# LED_Panel.net
KiCad netlist of a schematic drawn in Altium Designer
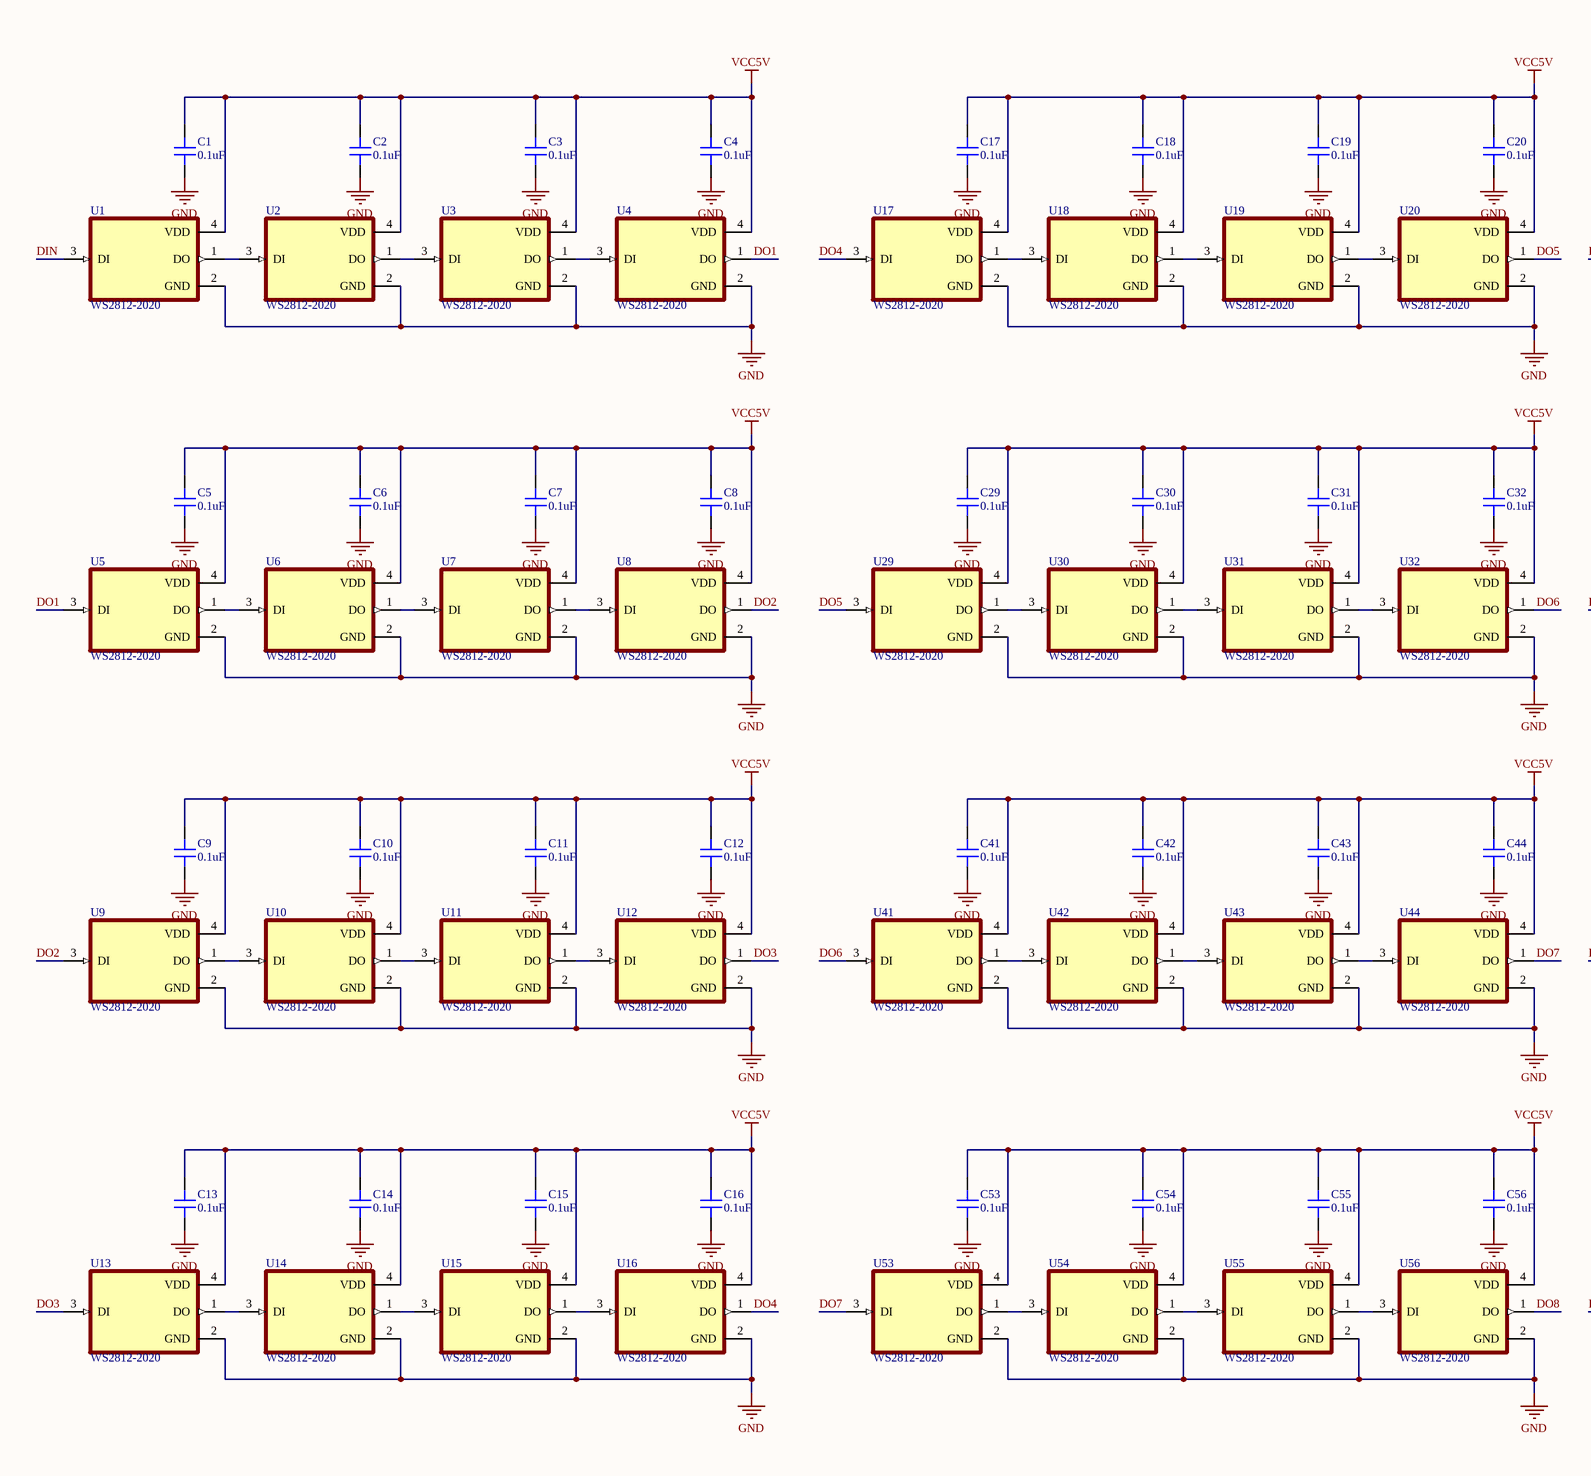
[diagram p0: LED_Panel.SchDoc, left]
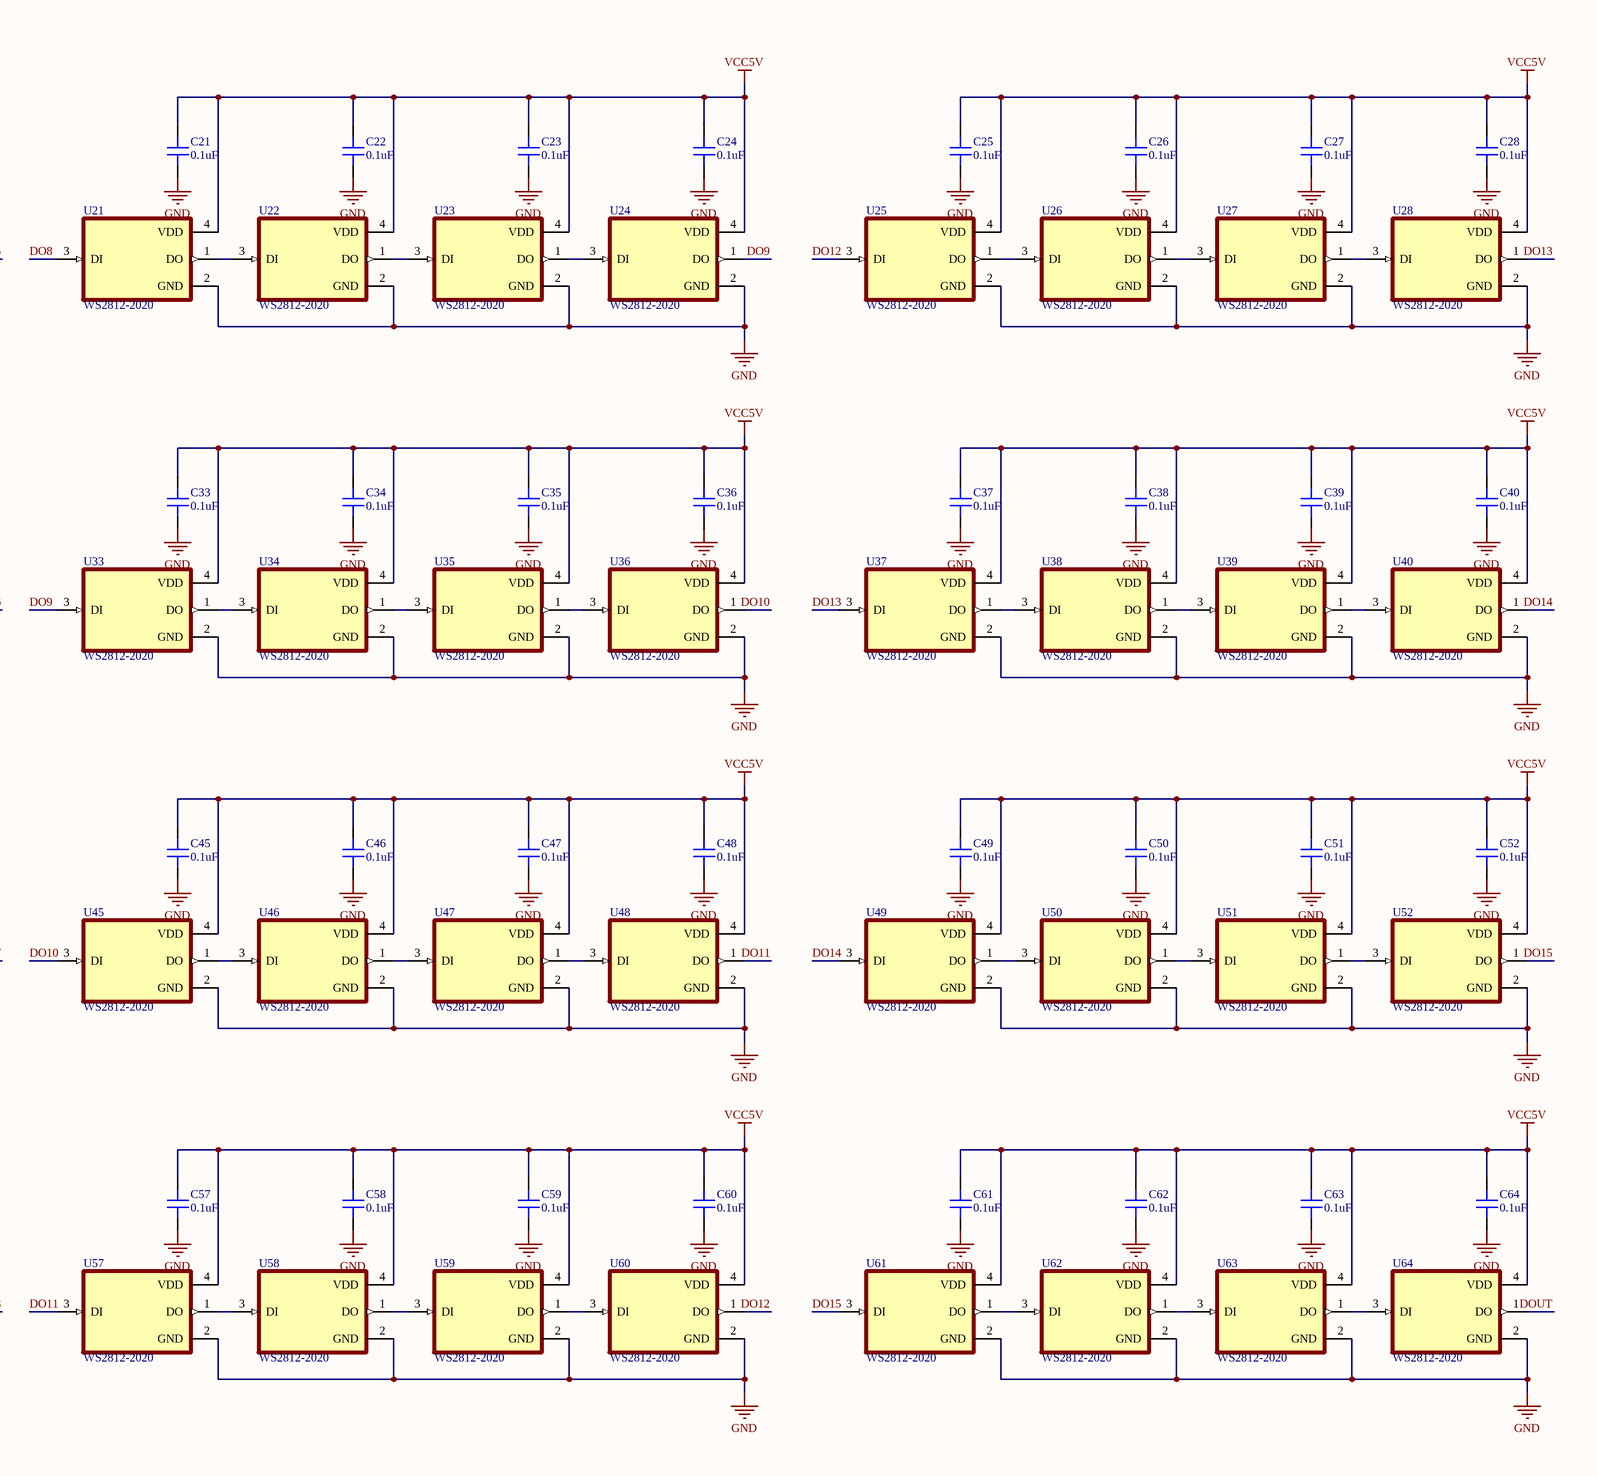
[diagram p1: LED_Panel.SchDoc, right]

(export (version "E")
  (design (tool "Eeschema 10.0.6"))
  (components
    (comp (ref "C1")
      (value "0.1uF")
      (footprint "CAP 0603_1608")
      (description "CAP CER 2700PF 25V NP0 0603")
      (fields
        (field (name "PART NUMBER") "C0603C272F3GAC7867")
        (field (name "MANUFACTURER") "KEMET")
        (field (name "LASTUPDATED") "2022/5/23 下午 12:55:07")
      )
      (libsource (lib "Celestial Altium Library - altium_library") (part "Capacitor"))
    )
    (comp (ref "C2")
      (value "0.1uF")
      (footprint "CAP 0603_1608")
      (description "CAP CER 2700PF 25V NP0 0603")
      (fields
        (field (name "PART NUMBER") "C0603C272F3GAC7867")
        (field (name "MANUFACTURER") "KEMET")
        (field (name "LASTUPDATED") "2022/5/23 下午 12:55:07")
      )
      (libsource (lib "Celestial Altium Library - altium_library") (part "Capacitor"))
    )
    (comp (ref "C3")
      (value "0.1uF")
      (footprint "CAP 0603_1608")
      (description "CAP CER 2700PF 25V NP0 0603")
      (fields
        (field (name "PART NUMBER") "C0603C272F3GAC7867")
        (field (name "MANUFACTURER") "KEMET")
        (field (name "LASTUPDATED") "2022/5/23 下午 12:55:07")
      )
      (libsource (lib "Celestial Altium Library - altium_library") (part "Capacitor"))
    )
    (comp (ref "C4")
      (value "0.1uF")
      (footprint "CAP 0603_1608")
      (description "CAP CER 2700PF 25V NP0 0603")
      (fields
        (field (name "PART NUMBER") "C0603C272F3GAC7867")
        (field (name "MANUFACTURER") "KEMET")
        (field (name "LASTUPDATED") "2022/5/23 下午 12:55:07")
      )
      (libsource (lib "Celestial Altium Library - altium_library") (part "Capacitor"))
    )
    (comp (ref "C5")
      (value "0.1uF")
      (footprint "CAP 0603_1608")
      (description "CAP CER 2700PF 25V NP0 0603")
      (fields
        (field (name "PART NUMBER") "C0603C272F3GAC7867")
        (field (name "MANUFACTURER") "KEMET")
        (field (name "LASTUPDATED") "2022/5/23 下午 12:55:07")
      )
      (libsource (lib "Celestial Altium Library - altium_library") (part "Capacitor"))
    )
    (comp (ref "C6")
      (value "0.1uF")
      (footprint "CAP 0603_1608")
      (description "CAP CER 2700PF 25V NP0 0603")
      (fields
        (field (name "PART NUMBER") "C0603C272F3GAC7867")
        (field (name "MANUFACTURER") "KEMET")
        (field (name "LASTUPDATED") "2022/5/23 下午 12:55:07")
      )
      (libsource (lib "Celestial Altium Library - altium_library") (part "Capacitor"))
    )
    (comp (ref "C7")
      (value "0.1uF")
      (footprint "CAP 0603_1608")
      (description "CAP CER 2700PF 25V NP0 0603")
      (fields
        (field (name "PART NUMBER") "C0603C272F3GAC7867")
        (field (name "MANUFACTURER") "KEMET")
        (field (name "LASTUPDATED") "2022/5/23 下午 12:55:07")
      )
      (libsource (lib "Celestial Altium Library - altium_library") (part "Capacitor"))
    )
    (comp (ref "C8")
      (value "0.1uF")
      (footprint "CAP 0603_1608")
      (description "CAP CER 2700PF 25V NP0 0603")
      (fields
        (field (name "PART NUMBER") "C0603C272F3GAC7867")
        (field (name "MANUFACTURER") "KEMET")
        (field (name "LASTUPDATED") "2022/5/23 下午 12:55:07")
      )
      (libsource (lib "Celestial Altium Library - altium_library") (part "Capacitor"))
    )
    (comp (ref "C9")
      (value "0.1uF")
      (footprint "CAP 0603_1608")
      (description "CAP CER 2700PF 25V NP0 0603")
      (fields
        (field (name "PART NUMBER") "C0603C272F3GAC7867")
        (field (name "MANUFACTURER") "KEMET")
        (field (name "LASTUPDATED") "2022/5/23 下午 12:55:07")
      )
      (libsource (lib "Celestial Altium Library - altium_library") (part "Capacitor"))
    )
    (comp (ref "C10")
      (value "0.1uF")
      (footprint "CAP 0603_1608")
      (description "CAP CER 2700PF 25V NP0 0603")
      (fields
        (field (name "PART NUMBER") "C0603C272F3GAC7867")
        (field (name "MANUFACTURER") "KEMET")
        (field (name "LASTUPDATED") "2022/5/23 下午 12:55:07")
      )
      (libsource (lib "Celestial Altium Library - altium_library") (part "Capacitor"))
    )
    (comp (ref "C11")
      (value "0.1uF")
      (footprint "CAP 0603_1608")
      (description "CAP CER 2700PF 25V NP0 0603")
      (fields
        (field (name "PART NUMBER") "C0603C272F3GAC7867")
        (field (name "MANUFACTURER") "KEMET")
        (field (name "LASTUPDATED") "2022/5/23 下午 12:55:07")
      )
      (libsource (lib "Celestial Altium Library - altium_library") (part "Capacitor"))
    )
    (comp (ref "C12")
      (value "0.1uF")
      (footprint "CAP 0603_1608")
      (description "CAP CER 2700PF 25V NP0 0603")
      (fields
        (field (name "PART NUMBER") "C0603C272F3GAC7867")
        (field (name "MANUFACTURER") "KEMET")
        (field (name "LASTUPDATED") "2022/5/23 下午 12:55:07")
      )
      (libsource (lib "Celestial Altium Library - altium_library") (part "Capacitor"))
    )
    (comp (ref "C13")
      (value "0.1uF")
      (footprint "CAP 0603_1608")
      (description "CAP CER 2700PF 25V NP0 0603")
      (fields
        (field (name "PART NUMBER") "C0603C272F3GAC7867")
        (field (name "MANUFACTURER") "KEMET")
        (field (name "LASTUPDATED") "2022/5/23 下午 12:55:07")
      )
      (libsource (lib "Celestial Altium Library - altium_library") (part "Capacitor"))
    )
    (comp (ref "C14")
      (value "0.1uF")
      (footprint "CAP 0603_1608")
      (description "CAP CER 2700PF 25V NP0 0603")
      (fields
        (field (name "PART NUMBER") "C0603C272F3GAC7867")
        (field (name "MANUFACTURER") "KEMET")
        (field (name "LASTUPDATED") "2022/5/23 下午 12:55:07")
      )
      (libsource (lib "Celestial Altium Library - altium_library") (part "Capacitor"))
    )
    (comp (ref "C15")
      (value "0.1uF")
      (footprint "CAP 0603_1608")
      (description "CAP CER 2700PF 25V NP0 0603")
      (fields
        (field (name "PART NUMBER") "C0603C272F3GAC7867")
        (field (name "MANUFACTURER") "KEMET")
        (field (name "LASTUPDATED") "2022/5/23 下午 12:55:07")
      )
      (libsource (lib "Celestial Altium Library - altium_library") (part "Capacitor"))
    )
    (comp (ref "C16")
      (value "0.1uF")
      (footprint "CAP 0603_1608")
      (description "CAP CER 2700PF 25V NP0 0603")
      (fields
        (field (name "PART NUMBER") "C0603C272F3GAC7867")
        (field (name "MANUFACTURER") "KEMET")
        (field (name "LASTUPDATED") "2022/5/23 下午 12:55:07")
      )
      (libsource (lib "Celestial Altium Library - altium_library") (part "Capacitor"))
    )
    (comp (ref "C17")
      (value "0.1uF")
      (footprint "CAP 0603_1608")
      (description "CAP CER 2700PF 25V NP0 0603")
      (fields
        (field (name "PART NUMBER") "C0603C272F3GAC7867")
        (field (name "MANUFACTURER") "KEMET")
        (field (name "LASTUPDATED") "2022/5/23 下午 12:55:07")
      )
      (libsource (lib "Celestial Altium Library - altium_library") (part "Capacitor"))
    )
    (comp (ref "C18")
      (value "0.1uF")
      (footprint "CAP 0603_1608")
      (description "CAP CER 2700PF 25V NP0 0603")
      (fields
        (field (name "PART NUMBER") "C0603C272F3GAC7867")
        (field (name "MANUFACTURER") "KEMET")
        (field (name "LASTUPDATED") "2022/5/23 下午 12:55:07")
      )
      (libsource (lib "Celestial Altium Library - altium_library") (part "Capacitor"))
    )
    (comp (ref "C19")
      (value "0.1uF")
      (footprint "CAP 0603_1608")
      (description "CAP CER 2700PF 25V NP0 0603")
      (fields
        (field (name "PART NUMBER") "C0603C272F3GAC7867")
        (field (name "MANUFACTURER") "KEMET")
        (field (name "LASTUPDATED") "2022/5/23 下午 12:55:07")
      )
      (libsource (lib "Celestial Altium Library - altium_library") (part "Capacitor"))
    )
    (comp (ref "C20")
      (value "0.1uF")
      (footprint "CAP 0603_1608")
      (description "CAP CER 2700PF 25V NP0 0603")
      (fields
        (field (name "PART NUMBER") "C0603C272F3GAC7867")
        (field (name "MANUFACTURER") "KEMET")
        (field (name "LASTUPDATED") "2022/5/23 下午 12:55:07")
      )
      (libsource (lib "Celestial Altium Library - altium_library") (part "Capacitor"))
    )
    (comp (ref "C21")
      (value "0.1uF")
      (footprint "CAP 0603_1608")
      (description "CAP CER 2700PF 25V NP0 0603")
      (fields
        (field (name "PART NUMBER") "C0603C272F3GAC7867")
        (field (name "MANUFACTURER") "KEMET")
        (field (name "LASTUPDATED") "2022/5/23 下午 12:55:07")
      )
      (libsource (lib "Celestial Altium Library - altium_library") (part "Capacitor"))
    )
    (comp (ref "C22")
      (value "0.1uF")
      (footprint "CAP 0603_1608")
      (description "CAP CER 2700PF 25V NP0 0603")
      (fields
        (field (name "PART NUMBER") "C0603C272F3GAC7867")
        (field (name "MANUFACTURER") "KEMET")
        (field (name "LASTUPDATED") "2022/5/23 下午 12:55:07")
      )
      (libsource (lib "Celestial Altium Library - altium_library") (part "Capacitor"))
    )
    (comp (ref "C23")
      (value "0.1uF")
      (footprint "CAP 0603_1608")
      (description "CAP CER 2700PF 25V NP0 0603")
      (fields
        (field (name "PART NUMBER") "C0603C272F3GAC7867")
        (field (name "MANUFACTURER") "KEMET")
        (field (name "LASTUPDATED") "2022/5/23 下午 12:55:07")
      )
      (libsource (lib "Celestial Altium Library - altium_library") (part "Capacitor"))
    )
    (comp (ref "C24")
      (value "0.1uF")
      (footprint "CAP 0603_1608")
      (description "CAP CER 2700PF 25V NP0 0603")
      (fields
        (field (name "PART NUMBER") "C0603C272F3GAC7867")
        (field (name "MANUFACTURER") "KEMET")
        (field (name "LASTUPDATED") "2022/5/23 下午 12:55:07")
      )
      (libsource (lib "Celestial Altium Library - altium_library") (part "Capacitor"))
    )
    (comp (ref "C25")
      (value "0.1uF")
      (footprint "CAP 0603_1608")
      (description "CAP CER 2700PF 25V NP0 0603")
      (fields
        (field (name "PART NUMBER") "C0603C272F3GAC7867")
        (field (name "MANUFACTURER") "KEMET")
        (field (name "LASTUPDATED") "2022/5/23 下午 12:55:07")
      )
      (libsource (lib "Celestial Altium Library - altium_library") (part "Capacitor"))
    )
    (comp (ref "C26")
      (value "0.1uF")
      (footprint "CAP 0603_1608")
      (description "CAP CER 2700PF 25V NP0 0603")
      (fields
        (field (name "PART NUMBER") "C0603C272F3GAC7867")
        (field (name "MANUFACTURER") "KEMET")
        (field (name "LASTUPDATED") "2022/5/23 下午 12:55:07")
      )
      (libsource (lib "Celestial Altium Library - altium_library") (part "Capacitor"))
    )
    (comp (ref "C27")
      (value "0.1uF")
      (footprint "CAP 0603_1608")
      (description "CAP CER 2700PF 25V NP0 0603")
      (fields
        (field (name "PART NUMBER") "C0603C272F3GAC7867")
        (field (name "MANUFACTURER") "KEMET")
        (field (name "LASTUPDATED") "2022/5/23 下午 12:55:07")
      )
      (libsource (lib "Celestial Altium Library - altium_library") (part "Capacitor"))
    )
    (comp (ref "C28")
      (value "0.1uF")
      (footprint "CAP 0603_1608")
      (description "CAP CER 2700PF 25V NP0 0603")
      (fields
        (field (name "PART NUMBER") "C0603C272F3GAC7867")
        (field (name "MANUFACTURER") "KEMET")
        (field (name "LASTUPDATED") "2022/5/23 下午 12:55:07")
      )
      (libsource (lib "Celestial Altium Library - altium_library") (part "Capacitor"))
    )
    (comp (ref "C29")
      (value "0.1uF")
      (footprint "CAP 0603_1608")
      (description "CAP CER 2700PF 25V NP0 0603")
      (fields
        (field (name "PART NUMBER") "C0603C272F3GAC7867")
        (field (name "MANUFACTURER") "KEMET")
        (field (name "LASTUPDATED") "2022/5/23 下午 12:55:07")
      )
      (libsource (lib "Celestial Altium Library - altium_library") (part "Capacitor"))
    )
    (comp (ref "C30")
      (value "0.1uF")
      (footprint "CAP 0603_1608")
      (description "CAP CER 2700PF 25V NP0 0603")
      (fields
        (field (name "PART NUMBER") "C0603C272F3GAC7867")
        (field (name "MANUFACTURER") "KEMET")
        (field (name "LASTUPDATED") "2022/5/23 下午 12:55:07")
      )
      (libsource (lib "Celestial Altium Library - altium_library") (part "Capacitor"))
    )
    (comp (ref "C31")
      (value "0.1uF")
      (footprint "CAP 0603_1608")
      (description "CAP CER 2700PF 25V NP0 0603")
      (fields
        (field (name "PART NUMBER") "C0603C272F3GAC7867")
        (field (name "MANUFACTURER") "KEMET")
        (field (name "LASTUPDATED") "2022/5/23 下午 12:55:07")
      )
      (libsource (lib "Celestial Altium Library - altium_library") (part "Capacitor"))
    )
    (comp (ref "C32")
      (value "0.1uF")
      (footprint "CAP 0603_1608")
      (description "CAP CER 2700PF 25V NP0 0603")
      (fields
        (field (name "PART NUMBER") "C0603C272F3GAC7867")
        (field (name "MANUFACTURER") "KEMET")
        (field (name "LASTUPDATED") "2022/5/23 下午 12:55:07")
      )
      (libsource (lib "Celestial Altium Library - altium_library") (part "Capacitor"))
    )
    (comp (ref "C33")
      (value "0.1uF")
      (footprint "CAP 0603_1608")
      (description "CAP CER 2700PF 25V NP0 0603")
      (fields
        (field (name "PART NUMBER") "C0603C272F3GAC7867")
        (field (name "MANUFACTURER") "KEMET")
        (field (name "LASTUPDATED") "2022/5/23 下午 12:55:07")
      )
      (libsource (lib "Celestial Altium Library - altium_library") (part "Capacitor"))
    )
    (comp (ref "C34")
      (value "0.1uF")
      (footprint "CAP 0603_1608")
      (description "CAP CER 2700PF 25V NP0 0603")
      (fields
        (field (name "PART NUMBER") "C0603C272F3GAC7867")
        (field (name "MANUFACTURER") "KEMET")
        (field (name "LASTUPDATED") "2022/5/23 下午 12:55:07")
      )
      (libsource (lib "Celestial Altium Library - altium_library") (part "Capacitor"))
    )
    (comp (ref "C35")
      (value "0.1uF")
      (footprint "CAP 0603_1608")
      (description "CAP CER 2700PF 25V NP0 0603")
      (fields
        (field (name "PART NUMBER") "C0603C272F3GAC7867")
        (field (name "MANUFACTURER") "KEMET")
        (field (name "LASTUPDATED") "2022/5/23 下午 12:55:07")
      )
      (libsource (lib "Celestial Altium Library - altium_library") (part "Capacitor"))
    )
    (comp (ref "C36")
      (value "0.1uF")
      (footprint "CAP 0603_1608")
      (description "CAP CER 2700PF 25V NP0 0603")
      (fields
        (field (name "PART NUMBER") "C0603C272F3GAC7867")
        (field (name "MANUFACTURER") "KEMET")
        (field (name "LASTUPDATED") "2022/5/23 下午 12:55:07")
      )
      (libsource (lib "Celestial Altium Library - altium_library") (part "Capacitor"))
    )
    (comp (ref "C37")
      (value "0.1uF")
      (footprint "CAP 0603_1608")
      (description "CAP CER 2700PF 25V NP0 0603")
      (fields
        (field (name "PART NUMBER") "C0603C272F3GAC7867")
        (field (name "MANUFACTURER") "KEMET")
        (field (name "LASTUPDATED") "2022/5/23 下午 12:55:07")
      )
      (libsource (lib "Celestial Altium Library - altium_library") (part "Capacitor"))
    )
    (comp (ref "C38")
      (value "0.1uF")
      (footprint "CAP 0603_1608")
      (description "CAP CER 2700PF 25V NP0 0603")
      (fields
        (field (name "PART NUMBER") "C0603C272F3GAC7867")
        (field (name "MANUFACTURER") "KEMET")
        (field (name "LASTUPDATED") "2022/5/23 下午 12:55:07")
      )
      (libsource (lib "Celestial Altium Library - altium_library") (part "Capacitor"))
    )
    (comp (ref "C39")
      (value "0.1uF")
      (footprint "CAP 0603_1608")
      (description "CAP CER 2700PF 25V NP0 0603")
      (fields
        (field (name "PART NUMBER") "C0603C272F3GAC7867")
        (field (name "MANUFACTURER") "KEMET")
        (field (name "LASTUPDATED") "2022/5/23 下午 12:55:07")
      )
      (libsource (lib "Celestial Altium Library - altium_library") (part "Capacitor"))
    )
    (comp (ref "C40")
      (value "0.1uF")
      (footprint "CAP 0603_1608")
      (description "CAP CER 2700PF 25V NP0 0603")
      (fields
        (field (name "PART NUMBER") "C0603C272F3GAC7867")
        (field (name "MANUFACTURER") "KEMET")
        (field (name "LASTUPDATED") "2022/5/23 下午 12:55:07")
      )
      (libsource (lib "Celestial Altium Library - altium_library") (part "Capacitor"))
    )
    (comp (ref "C41")
      (value "0.1uF")
      (footprint "CAP 0603_1608")
      (description "CAP CER 2700PF 25V NP0 0603")
      (fields
        (field (name "PART NUMBER") "C0603C272F3GAC7867")
        (field (name "MANUFACTURER") "KEMET")
        (field (name "LASTUPDATED") "2022/5/23 下午 12:55:07")
      )
      (libsource (lib "Celestial Altium Library - altium_library") (part "Capacitor"))
    )
    (comp (ref "C42")
      (value "0.1uF")
      (footprint "CAP 0603_1608")
      (description "CAP CER 2700PF 25V NP0 0603")
      (fields
        (field (name "PART NUMBER") "C0603C272F3GAC7867")
        (field (name "MANUFACTURER") "KEMET")
        (field (name "LASTUPDATED") "2022/5/23 下午 12:55:07")
      )
      (libsource (lib "Celestial Altium Library - altium_library") (part "Capacitor"))
    )
    (comp (ref "C43")
      (value "0.1uF")
      (footprint "CAP 0603_1608")
      (description "CAP CER 2700PF 25V NP0 0603")
      (fields
        (field (name "PART NUMBER") "C0603C272F3GAC7867")
        (field (name "MANUFACTURER") "KEMET")
        (field (name "LASTUPDATED") "2022/5/23 下午 12:55:07")
      )
      (libsource (lib "Celestial Altium Library - altium_library") (part "Capacitor"))
    )
    (comp (ref "C44")
      (value "0.1uF")
      (footprint "CAP 0603_1608")
      (description "CAP CER 2700PF 25V NP0 0603")
      (fields
        (field (name "PART NUMBER") "C0603C272F3GAC7867")
        (field (name "MANUFACTURER") "KEMET")
        (field (name "LASTUPDATED") "2022/5/23 下午 12:55:07")
      )
      (libsource (lib "Celestial Altium Library - altium_library") (part "Capacitor"))
    )
    (comp (ref "C45")
      (value "0.1uF")
      (footprint "CAP 0603_1608")
      (description "CAP CER 2700PF 25V NP0 0603")
      (fields
        (field (name "PART NUMBER") "C0603C272F3GAC7867")
        (field (name "MANUFACTURER") "KEMET")
        (field (name "LASTUPDATED") "2022/5/23 下午 12:55:07")
      )
      (libsource (lib "Celestial Altium Library - altium_library") (part "Capacitor"))
    )
    (comp (ref "C46")
      (value "0.1uF")
      (footprint "CAP 0603_1608")
      (description "CAP CER 2700PF 25V NP0 0603")
      (fields
        (field (name "PART NUMBER") "C0603C272F3GAC7867")
        (field (name "MANUFACTURER") "KEMET")
        (field (name "LASTUPDATED") "2022/5/23 下午 12:55:07")
      )
      (libsource (lib "Celestial Altium Library - altium_library") (part "Capacitor"))
    )
    (comp (ref "C47")
      (value "0.1uF")
      (footprint "CAP 0603_1608")
      (description "CAP CER 2700PF 25V NP0 0603")
      (fields
        (field (name "PART NUMBER") "C0603C272F3GAC7867")
        (field (name "MANUFACTURER") "KEMET")
        (field (name "LASTUPDATED") "2022/5/23 下午 12:55:07")
      )
      (libsource (lib "Celestial Altium Library - altium_library") (part "Capacitor"))
    )
    (comp (ref "C48")
      (value "0.1uF")
      (footprint "CAP 0603_1608")
      (description "CAP CER 2700PF 25V NP0 0603")
      (fields
        (field (name "PART NUMBER") "C0603C272F3GAC7867")
        (field (name "MANUFACTURER") "KEMET")
        (field (name "LASTUPDATED") "2022/5/23 下午 12:55:07")
      )
      (libsource (lib "Celestial Altium Library - altium_library") (part "Capacitor"))
    )
    (comp (ref "C49")
      (value "0.1uF")
      (footprint "CAP 0603_1608")
      (description "CAP CER 2700PF 25V NP0 0603")
      (fields
        (field (name "PART NUMBER") "C0603C272F3GAC7867")
        (field (name "MANUFACTURER") "KEMET")
        (field (name "LASTUPDATED") "2022/5/23 下午 12:55:07")
      )
      (libsource (lib "Celestial Altium Library - altium_library") (part "Capacitor"))
    )
    (comp (ref "C50")
      (value "0.1uF")
      (footprint "CAP 0603_1608")
      (description "CAP CER 2700PF 25V NP0 0603")
      (fields
        (field (name "PART NUMBER") "C0603C272F3GAC7867")
        (field (name "MANUFACTURER") "KEMET")
        (field (name "LASTUPDATED") "2022/5/23 下午 12:55:07")
      )
      (libsource (lib "Celestial Altium Library - altium_library") (part "Capacitor"))
    )
    (comp (ref "C51")
      (value "0.1uF")
      (footprint "CAP 0603_1608")
      (description "CAP CER 2700PF 25V NP0 0603")
      (fields
        (field (name "PART NUMBER") "C0603C272F3GAC7867")
        (field (name "MANUFACTURER") "KEMET")
        (field (name "LASTUPDATED") "2022/5/23 下午 12:55:07")
      )
      (libsource (lib "Celestial Altium Library - altium_library") (part "Capacitor"))
    )
    (comp (ref "C52")
      (value "0.1uF")
      (footprint "CAP 0603_1608")
      (description "CAP CER 2700PF 25V NP0 0603")
      (fields
        (field (name "PART NUMBER") "C0603C272F3GAC7867")
        (field (name "MANUFACTURER") "KEMET")
        (field (name "LASTUPDATED") "2022/5/23 下午 12:55:07")
      )
      (libsource (lib "Celestial Altium Library - altium_library") (part "Capacitor"))
    )
    (comp (ref "C53")
      (value "0.1uF")
      (footprint "CAP 0603_1608")
      (description "CAP CER 2700PF 25V NP0 0603")
      (fields
        (field (name "PART NUMBER") "C0603C272F3GAC7867")
        (field (name "MANUFACTURER") "KEMET")
        (field (name "LASTUPDATED") "2022/5/23 下午 12:55:07")
      )
      (libsource (lib "Celestial Altium Library - altium_library") (part "Capacitor"))
    )
    (comp (ref "C54")
      (value "0.1uF")
      (footprint "CAP 0603_1608")
      (description "CAP CER 2700PF 25V NP0 0603")
      (fields
        (field (name "PART NUMBER") "C0603C272F3GAC7867")
        (field (name "MANUFACTURER") "KEMET")
        (field (name "LASTUPDATED") "2022/5/23 下午 12:55:07")
      )
      (libsource (lib "Celestial Altium Library - altium_library") (part "Capacitor"))
    )
    (comp (ref "C55")
      (value "0.1uF")
      (footprint "CAP 0603_1608")
      (description "CAP CER 2700PF 25V NP0 0603")
      (fields
        (field (name "PART NUMBER") "C0603C272F3GAC7867")
        (field (name "MANUFACTURER") "KEMET")
        (field (name "LASTUPDATED") "2022/5/23 下午 12:55:07")
      )
      (libsource (lib "Celestial Altium Library - altium_library") (part "Capacitor"))
    )
    (comp (ref "C56")
      (value "0.1uF")
      (footprint "CAP 0603_1608")
      (description "CAP CER 2700PF 25V NP0 0603")
      (fields
        (field (name "PART NUMBER") "C0603C272F3GAC7867")
        (field (name "MANUFACTURER") "KEMET")
        (field (name "LASTUPDATED") "2022/5/23 下午 12:55:07")
      )
      (libsource (lib "Celestial Altium Library - altium_library") (part "Capacitor"))
    )
    (comp (ref "C57")
      (value "0.1uF")
      (footprint "CAP 0603_1608")
      (description "CAP CER 2700PF 25V NP0 0603")
      (fields
        (field (name "PART NUMBER") "C0603C272F3GAC7867")
        (field (name "MANUFACTURER") "KEMET")
        (field (name "LASTUPDATED") "2022/5/23 下午 12:55:07")
      )
      (libsource (lib "Celestial Altium Library - altium_library") (part "Capacitor"))
    )
    (comp (ref "C58")
      (value "0.1uF")
      (footprint "CAP 0603_1608")
      (description "CAP CER 2700PF 25V NP0 0603")
      (fields
        (field (name "PART NUMBER") "C0603C272F3GAC7867")
        (field (name "MANUFACTURER") "KEMET")
        (field (name "LASTUPDATED") "2022/5/23 下午 12:55:07")
      )
      (libsource (lib "Celestial Altium Library - altium_library") (part "Capacitor"))
    )
    (comp (ref "C59")
      (value "0.1uF")
      (footprint "CAP 0603_1608")
      (description "CAP CER 2700PF 25V NP0 0603")
      (fields
        (field (name "PART NUMBER") "C0603C272F3GAC7867")
        (field (name "MANUFACTURER") "KEMET")
        (field (name "LASTUPDATED") "2022/5/23 下午 12:55:07")
      )
      (libsource (lib "Celestial Altium Library - altium_library") (part "Capacitor"))
    )
    (comp (ref "C60")
      (value "0.1uF")
      (footprint "CAP 0603_1608")
      (description "CAP CER 2700PF 25V NP0 0603")
      (fields
        (field (name "PART NUMBER") "C0603C272F3GAC7867")
        (field (name "MANUFACTURER") "KEMET")
        (field (name "LASTUPDATED") "2022/5/23 下午 12:55:07")
      )
      (libsource (lib "Celestial Altium Library - altium_library") (part "Capacitor"))
    )
    (comp (ref "C61")
      (value "0.1uF")
      (footprint "CAP 0603_1608")
      (description "CAP CER 2700PF 25V NP0 0603")
      (fields
        (field (name "PART NUMBER") "C0603C272F3GAC7867")
        (field (name "MANUFACTURER") "KEMET")
        (field (name "LASTUPDATED") "2022/5/23 下午 12:55:07")
      )
      (libsource (lib "Celestial Altium Library - altium_library") (part "Capacitor"))
    )
    (comp (ref "C62")
      (value "0.1uF")
      (footprint "CAP 0603_1608")
      (description "CAP CER 2700PF 25V NP0 0603")
      (fields
        (field (name "PART NUMBER") "C0603C272F3GAC7867")
        (field (name "MANUFACTURER") "KEMET")
        (field (name "LASTUPDATED") "2022/5/23 下午 12:55:07")
      )
      (libsource (lib "Celestial Altium Library - altium_library") (part "Capacitor"))
    )
    (comp (ref "C63")
      (value "0.1uF")
      (footprint "CAP 0603_1608")
      (description "CAP CER 2700PF 25V NP0 0603")
      (fields
        (field (name "PART NUMBER") "C0603C272F3GAC7867")
        (field (name "MANUFACTURER") "KEMET")
        (field (name "LASTUPDATED") "2022/5/23 下午 12:55:07")
      )
      (libsource (lib "Celestial Altium Library - altium_library") (part "Capacitor"))
    )
    (comp (ref "C64")
      (value "0.1uF")
      (footprint "CAP 0603_1608")
      (description "CAP CER 2700PF 25V NP0 0603")
      (fields
        (field (name "PART NUMBER") "C0603C272F3GAC7867")
        (field (name "MANUFACTURER") "KEMET")
        (field (name "LASTUPDATED") "2022/5/23 下午 12:55:07")
      )
      (libsource (lib "Celestial Altium Library - altium_library") (part "Capacitor"))
    )
    (comp (ref "U1")
      (value "WS2812-2020")
      (footprint "LED_WS2812-2020")
      (fields (field (name "MF") "{'manufacturer': u'Worldsemi'}"))
      (libsource (lib "SnapEDA_Library") (part "WS2812-2020"))
    )
    (comp (ref "U2")
      (value "WS2812-2020")
      (footprint "LED_WS2812-2020")
      (fields (field (name "MF") "{'manufacturer': u'Worldsemi'}"))
      (libsource (lib "SnapEDA_Library") (part "WS2812-2020"))
    )
    (comp (ref "U3")
      (value "WS2812-2020")
      (footprint "LED_WS2812-2020")
      (fields (field (name "MF") "{'manufacturer': u'Worldsemi'}"))
      (libsource (lib "SnapEDA_Library") (part "WS2812-2020"))
    )
    (comp (ref "U4")
      (value "WS2812-2020")
      (footprint "LED_WS2812-2020")
      (fields (field (name "MF") "{'manufacturer': u'Worldsemi'}"))
      (libsource (lib "SnapEDA_Library") (part "WS2812-2020"))
    )
    (comp (ref "U5")
      (value "WS2812-2020")
      (footprint "LED_WS2812-2020")
      (fields (field (name "MF") "{'manufacturer': u'Worldsemi'}"))
      (libsource (lib "SnapEDA_Library") (part "WS2812-2020"))
    )
    (comp (ref "U6")
      (value "WS2812-2020")
      (footprint "LED_WS2812-2020")
      (fields (field (name "MF") "{'manufacturer': u'Worldsemi'}"))
      (libsource (lib "SnapEDA_Library") (part "WS2812-2020"))
    )
    (comp (ref "U7")
      (value "WS2812-2020")
      (footprint "LED_WS2812-2020")
      (fields (field (name "MF") "{'manufacturer': u'Worldsemi'}"))
      (libsource (lib "SnapEDA_Library") (part "WS2812-2020"))
    )
    (comp (ref "U8")
      (value "WS2812-2020")
      (footprint "LED_WS2812-2020")
      (fields (field (name "MF") "{'manufacturer': u'Worldsemi'}"))
      (libsource (lib "SnapEDA_Library") (part "WS2812-2020"))
    )
    (comp (ref "U9")
      (value "WS2812-2020")
      (footprint "LED_WS2812-2020")
      (fields (field (name "MF") "{'manufacturer': u'Worldsemi'}"))
      (libsource (lib "SnapEDA_Library") (part "WS2812-2020"))
    )
    (comp (ref "U10")
      (value "WS2812-2020")
      (footprint "LED_WS2812-2020")
      (fields (field (name "MF") "{'manufacturer': u'Worldsemi'}"))
      (libsource (lib "SnapEDA_Library") (part "WS2812-2020"))
    )
    (comp (ref "U11")
      (value "WS2812-2020")
      (footprint "LED_WS2812-2020")
      (fields (field (name "MF") "{'manufacturer': u'Worldsemi'}"))
      (libsource (lib "SnapEDA_Library") (part "WS2812-2020"))
    )
    (comp (ref "U12")
      (value "WS2812-2020")
      (footprint "LED_WS2812-2020")
      (fields (field (name "MF") "{'manufacturer': u'Worldsemi'}"))
      (libsource (lib "SnapEDA_Library") (part "WS2812-2020"))
    )
    (comp (ref "U13")
      (value "WS2812-2020")
      (footprint "LED_WS2812-2020")
      (fields (field (name "MF") "{'manufacturer': u'Worldsemi'}"))
      (libsource (lib "SnapEDA_Library") (part "WS2812-2020"))
    )
    (comp (ref "U14")
      (value "WS2812-2020")
      (footprint "LED_WS2812-2020")
      (fields (field (name "MF") "{'manufacturer': u'Worldsemi'}"))
      (libsource (lib "SnapEDA_Library") (part "WS2812-2020"))
    )
    (comp (ref "U15")
      (value "WS2812-2020")
      (footprint "LED_WS2812-2020")
      (fields (field (name "MF") "{'manufacturer': u'Worldsemi'}"))
      (libsource (lib "SnapEDA_Library") (part "WS2812-2020"))
    )
    (comp (ref "U16")
      (value "WS2812-2020")
      (footprint "LED_WS2812-2020")
      (fields (field (name "MF") "{'manufacturer': u'Worldsemi'}"))
      (libsource (lib "SnapEDA_Library") (part "WS2812-2020"))
    )
    (comp (ref "U17")
      (value "WS2812-2020")
      (footprint "LED_WS2812-2020")
      (fields (field (name "MF") "{'manufacturer': u'Worldsemi'}"))
      (libsource (lib "SnapEDA_Library") (part "WS2812-2020"))
    )
    (comp (ref "U18")
      (value "WS2812-2020")
      (footprint "LED_WS2812-2020")
      (fields (field (name "MF") "{'manufacturer': u'Worldsemi'}"))
      (libsource (lib "SnapEDA_Library") (part "WS2812-2020"))
    )
    (comp (ref "U19")
      (value "WS2812-2020")
      (footprint "LED_WS2812-2020")
      (fields (field (name "MF") "{'manufacturer': u'Worldsemi'}"))
      (libsource (lib "SnapEDA_Library") (part "WS2812-2020"))
    )
    (comp (ref "U20")
      (value "WS2812-2020")
      (footprint "LED_WS2812-2020")
      (fields (field (name "MF") "{'manufacturer': u'Worldsemi'}"))
      (libsource (lib "SnapEDA_Library") (part "WS2812-2020"))
    )
    (comp (ref "U21")
      (value "WS2812-2020")
      (footprint "LED_WS2812-2020")
      (fields (field (name "MF") "{'manufacturer': u'Worldsemi'}"))
      (libsource (lib "SnapEDA_Library") (part "WS2812-2020"))
    )
    (comp (ref "U22")
      (value "WS2812-2020")
      (footprint "LED_WS2812-2020")
      (fields (field (name "MF") "{'manufacturer': u'Worldsemi'}"))
      (libsource (lib "SnapEDA_Library") (part "WS2812-2020"))
    )
    (comp (ref "U23")
      (value "WS2812-2020")
      (footprint "LED_WS2812-2020")
      (fields (field (name "MF") "{'manufacturer': u'Worldsemi'}"))
      (libsource (lib "SnapEDA_Library") (part "WS2812-2020"))
    )
    (comp (ref "U24")
      (value "WS2812-2020")
      (footprint "LED_WS2812-2020")
      (fields (field (name "MF") "{'manufacturer': u'Worldsemi'}"))
      (libsource (lib "SnapEDA_Library") (part "WS2812-2020"))
    )
    (comp (ref "U25")
      (value "WS2812-2020")
      (footprint "LED_WS2812-2020")
      (fields (field (name "MF") "{'manufacturer': u'Worldsemi'}"))
      (libsource (lib "SnapEDA_Library") (part "WS2812-2020"))
    )
    (comp (ref "U26")
      (value "WS2812-2020")
      (footprint "LED_WS2812-2020")
      (fields (field (name "MF") "{'manufacturer': u'Worldsemi'}"))
      (libsource (lib "SnapEDA_Library") (part "WS2812-2020"))
    )
    (comp (ref "U27")
      (value "WS2812-2020")
      (footprint "LED_WS2812-2020")
      (fields (field (name "MF") "{'manufacturer': u'Worldsemi'}"))
      (libsource (lib "SnapEDA_Library") (part "WS2812-2020"))
    )
    (comp (ref "U28")
      (value "WS2812-2020")
      (footprint "LED_WS2812-2020")
      (fields (field (name "MF") "{'manufacturer': u'Worldsemi'}"))
      (libsource (lib "SnapEDA_Library") (part "WS2812-2020"))
    )
    (comp (ref "U29")
      (value "WS2812-2020")
      (footprint "LED_WS2812-2020")
      (fields (field (name "MF") "{'manufacturer': u'Worldsemi'}"))
      (libsource (lib "SnapEDA_Library") (part "WS2812-2020"))
    )
    (comp (ref "U30")
      (value "WS2812-2020")
      (footprint "LED_WS2812-2020")
      (fields (field (name "MF") "{'manufacturer': u'Worldsemi'}"))
      (libsource (lib "SnapEDA_Library") (part "WS2812-2020"))
    )
    (comp (ref "U31")
      (value "WS2812-2020")
      (footprint "LED_WS2812-2020")
      (fields (field (name "MF") "{'manufacturer': u'Worldsemi'}"))
      (libsource (lib "SnapEDA_Library") (part "WS2812-2020"))
    )
    (comp (ref "U32")
      (value "WS2812-2020")
      (footprint "LED_WS2812-2020")
      (fields (field (name "MF") "{'manufacturer': u'Worldsemi'}"))
      (libsource (lib "SnapEDA_Library") (part "WS2812-2020"))
    )
    (comp (ref "U33")
      (value "WS2812-2020")
      (footprint "LED_WS2812-2020")
      (fields (field (name "MF") "{'manufacturer': u'Worldsemi'}"))
      (libsource (lib "SnapEDA_Library") (part "WS2812-2020"))
    )
    (comp (ref "U34")
      (value "WS2812-2020")
      (footprint "LED_WS2812-2020")
      (fields (field (name "MF") "{'manufacturer': u'Worldsemi'}"))
      (libsource (lib "SnapEDA_Library") (part "WS2812-2020"))
    )
    (comp (ref "U35")
      (value "WS2812-2020")
      (footprint "LED_WS2812-2020")
      (fields (field (name "MF") "{'manufacturer': u'Worldsemi'}"))
      (libsource (lib "SnapEDA_Library") (part "WS2812-2020"))
    )
    (comp (ref "U36")
      (value "WS2812-2020")
      (footprint "LED_WS2812-2020")
      (fields (field (name "MF") "{'manufacturer': u'Worldsemi'}"))
      (libsource (lib "SnapEDA_Library") (part "WS2812-2020"))
    )
    (comp (ref "U37")
      (value "WS2812-2020")
      (footprint "LED_WS2812-2020")
      (fields (field (name "MF") "{'manufacturer': u'Worldsemi'}"))
      (libsource (lib "SnapEDA_Library") (part "WS2812-2020"))
    )
    (comp (ref "U38")
      (value "WS2812-2020")
      (footprint "LED_WS2812-2020")
      (fields (field (name "MF") "{'manufacturer': u'Worldsemi'}"))
      (libsource (lib "SnapEDA_Library") (part "WS2812-2020"))
    )
    (comp (ref "U39")
      (value "WS2812-2020")
      (footprint "LED_WS2812-2020")
      (fields (field (name "MF") "{'manufacturer': u'Worldsemi'}"))
      (libsource (lib "SnapEDA_Library") (part "WS2812-2020"))
    )
    (comp (ref "U40")
      (value "WS2812-2020")
      (footprint "LED_WS2812-2020")
      (fields (field (name "MF") "{'manufacturer': u'Worldsemi'}"))
      (libsource (lib "SnapEDA_Library") (part "WS2812-2020"))
    )
    (comp (ref "U41")
      (value "WS2812-2020")
      (footprint "LED_WS2812-2020")
      (fields (field (name "MF") "{'manufacturer': u'Worldsemi'}"))
      (libsource (lib "SnapEDA_Library") (part "WS2812-2020"))
    )
    (comp (ref "U42")
      (value "WS2812-2020")
      (footprint "LED_WS2812-2020")
      (fields (field (name "MF") "{'manufacturer': u'Worldsemi'}"))
      (libsource (lib "SnapEDA_Library") (part "WS2812-2020"))
    )
    (comp (ref "U43")
      (value "WS2812-2020")
      (footprint "LED_WS2812-2020")
      (fields (field (name "MF") "{'manufacturer': u'Worldsemi'}"))
      (libsource (lib "SnapEDA_Library") (part "WS2812-2020"))
    )
    (comp (ref "U44")
      (value "WS2812-2020")
      (footprint "LED_WS2812-2020")
      (fields (field (name "MF") "{'manufacturer': u'Worldsemi'}"))
      (libsource (lib "SnapEDA_Library") (part "WS2812-2020"))
    )
    (comp (ref "U45")
      (value "WS2812-2020")
      (footprint "LED_WS2812-2020")
      (fields (field (name "MF") "{'manufacturer': u'Worldsemi'}"))
      (libsource (lib "SnapEDA_Library") (part "WS2812-2020"))
    )
    (comp (ref "U46")
      (value "WS2812-2020")
      (footprint "LED_WS2812-2020")
      (fields (field (name "MF") "{'manufacturer': u'Worldsemi'}"))
      (libsource (lib "SnapEDA_Library") (part "WS2812-2020"))
    )
    (comp (ref "U47")
      (value "WS2812-2020")
      (footprint "LED_WS2812-2020")
      (fields (field (name "MF") "{'manufacturer': u'Worldsemi'}"))
      (libsource (lib "SnapEDA_Library") (part "WS2812-2020"))
    )
    (comp (ref "U48")
      (value "WS2812-2020")
      (footprint "LED_WS2812-2020")
      (fields (field (name "MF") "{'manufacturer': u'Worldsemi'}"))
      (libsource (lib "SnapEDA_Library") (part "WS2812-2020"))
    )
    (comp (ref "U49")
      (value "WS2812-2020")
      (footprint "LED_WS2812-2020")
      (fields (field (name "MF") "{'manufacturer': u'Worldsemi'}"))
      (libsource (lib "SnapEDA_Library") (part "WS2812-2020"))
    )
    (comp (ref "U50")
      (value "WS2812-2020")
      (footprint "LED_WS2812-2020")
      (fields (field (name "MF") "{'manufacturer': u'Worldsemi'}"))
      (libsource (lib "SnapEDA_Library") (part "WS2812-2020"))
    )
    (comp (ref "U51")
      (value "WS2812-2020")
      (footprint "LED_WS2812-2020")
      (fields (field (name "MF") "{'manufacturer': u'Worldsemi'}"))
      (libsource (lib "SnapEDA_Library") (part "WS2812-2020"))
    )
    (comp (ref "U52")
      (value "WS2812-2020")
      (footprint "LED_WS2812-2020")
      (fields (field (name "MF") "{'manufacturer': u'Worldsemi'}"))
      (libsource (lib "SnapEDA_Library") (part "WS2812-2020"))
    )
    (comp (ref "U53")
      (value "WS2812-2020")
      (footprint "LED_WS2812-2020")
      (fields (field (name "MF") "{'manufacturer': u'Worldsemi'}"))
      (libsource (lib "SnapEDA_Library") (part "WS2812-2020"))
    )
    (comp (ref "U54")
      (value "WS2812-2020")
      (footprint "LED_WS2812-2020")
      (fields (field (name "MF") "{'manufacturer': u'Worldsemi'}"))
      (libsource (lib "SnapEDA_Library") (part "WS2812-2020"))
    )
    (comp (ref "U55")
      (value "WS2812-2020")
      (footprint "LED_WS2812-2020")
      (fields (field (name "MF") "{'manufacturer': u'Worldsemi'}"))
      (libsource (lib "SnapEDA_Library") (part "WS2812-2020"))
    )
    (comp (ref "U56")
      (value "WS2812-2020")
      (footprint "LED_WS2812-2020")
      (fields (field (name "MF") "{'manufacturer': u'Worldsemi'}"))
      (libsource (lib "SnapEDA_Library") (part "WS2812-2020"))
    )
    (comp (ref "U57")
      (value "WS2812-2020")
      (footprint "LED_WS2812-2020")
      (fields (field (name "MF") "{'manufacturer': u'Worldsemi'}"))
      (libsource (lib "SnapEDA_Library") (part "WS2812-2020"))
    )
    (comp (ref "U58")
      (value "WS2812-2020")
      (footprint "LED_WS2812-2020")
      (fields (field (name "MF") "{'manufacturer': u'Worldsemi'}"))
      (libsource (lib "SnapEDA_Library") (part "WS2812-2020"))
    )
    (comp (ref "U59")
      (value "WS2812-2020")
      (footprint "LED_WS2812-2020")
      (fields (field (name "MF") "{'manufacturer': u'Worldsemi'}"))
      (libsource (lib "SnapEDA_Library") (part "WS2812-2020"))
    )
    (comp (ref "U60")
      (value "WS2812-2020")
      (footprint "LED_WS2812-2020")
      (fields (field (name "MF") "{'manufacturer': u'Worldsemi'}"))
      (libsource (lib "SnapEDA_Library") (part "WS2812-2020"))
    )
    (comp (ref "U61")
      (value "WS2812-2020")
      (footprint "LED_WS2812-2020")
      (fields (field (name "MF") "{'manufacturer': u'Worldsemi'}"))
      (libsource (lib "SnapEDA_Library") (part "WS2812-2020"))
    )
    (comp (ref "U62")
      (value "WS2812-2020")
      (footprint "LED_WS2812-2020")
      (fields (field (name "MF") "{'manufacturer': u'Worldsemi'}"))
      (libsource (lib "SnapEDA_Library") (part "WS2812-2020"))
    )
    (comp (ref "U63")
      (value "WS2812-2020")
      (footprint "LED_WS2812-2020")
      (fields (field (name "MF") "{'manufacturer': u'Worldsemi'}"))
      (libsource (lib "SnapEDA_Library") (part "WS2812-2020"))
    )
    (comp (ref "U64")
      (value "WS2812-2020")
      (footprint "LED_WS2812-2020")
      (fields (field (name "MF") "{'manufacturer': u'Worldsemi'}"))
      (libsource (lib "SnapEDA_Library") (part "WS2812-2020"))
    )
  )
  (nets
    (net (code "1") (name "/DIN") (class "Default")
      (node (ref "U1") (pin "3") (pinfunction "DI_3") (pintype "input"))
    )
    (net (code "2") (name "/DO1") (class "Default")
      (node (ref "U4") (pin "1") (pinfunction "DO_1") (pintype "output"))
      (node (ref "U5") (pin "3") (pinfunction "DI_3") (pintype "input"))
    )
    (net (code "3") (name "/DO2") (class "Default")
      (node (ref "U8") (pin "1") (pinfunction "DO_1") (pintype "output"))
      (node (ref "U9") (pin "3") (pinfunction "DI_3") (pintype "input"))
    )
    (net (code "4") (name "/DO3") (class "Default")
      (node (ref "U12") (pin "1") (pinfunction "DO_1") (pintype "output"))
      (node (ref "U13") (pin "3") (pinfunction "DI_3") (pintype "input"))
    )
    (net (code "5") (name "/DO4") (class "Default")
      (node (ref "U16") (pin "1") (pinfunction "DO_1") (pintype "output"))
      (node (ref "U17") (pin "3") (pinfunction "DI_3") (pintype "input"))
    )
    (net (code "6") (name "/DO5") (class "Default")
      (node (ref "U20") (pin "1") (pinfunction "DO_1") (pintype "output"))
      (node (ref "U29") (pin "3") (pinfunction "DI_3") (pintype "input"))
    )
    (net (code "7") (name "/DO6") (class "Default")
      (node (ref "U32") (pin "1") (pinfunction "DO_1") (pintype "output"))
      (node (ref "U41") (pin "3") (pinfunction "DI_3") (pintype "input"))
    )
    (net (code "8") (name "/DO7") (class "Default")
      (node (ref "U44") (pin "1") (pinfunction "DO_1") (pintype "output"))
      (node (ref "U53") (pin "3") (pinfunction "DI_3") (pintype "input"))
    )
    (net (code "9") (name "/DO8") (class "Default")
      (node (ref "U21") (pin "3") (pinfunction "DI_3") (pintype "input"))
      (node (ref "U56") (pin "1") (pinfunction "DO_1") (pintype "output"))
    )
    (net (code "10") (name "/DO9") (class "Default")
      (node (ref "U24") (pin "1") (pinfunction "DO_1") (pintype "output"))
      (node (ref "U33") (pin "3") (pinfunction "DI_3") (pintype "input"))
    )
    (net (code "11") (name "/DO10") (class "Default")
      (node (ref "U36") (pin "1") (pinfunction "DO_1") (pintype "output"))
      (node (ref "U45") (pin "3") (pinfunction "DI_3") (pintype "input"))
    )
    (net (code "12") (name "/DO11") (class "Default")
      (node (ref "U48") (pin "1") (pinfunction "DO_1") (pintype "output"))
      (node (ref "U57") (pin "3") (pinfunction "DI_3") (pintype "input"))
    )
    (net (code "13") (name "/DO12") (class "Default")
      (node (ref "U25") (pin "3") (pinfunction "DI_3") (pintype "input"))
      (node (ref "U60") (pin "1") (pinfunction "DO_1") (pintype "output"))
    )
    (net (code "14") (name "/DO13") (class "Default")
      (node (ref "U28") (pin "1") (pinfunction "DO_1") (pintype "output"))
      (node (ref "U37") (pin "3") (pinfunction "DI_3") (pintype "input"))
    )
    (net (code "15") (name "/DO14") (class "Default")
      (node (ref "U40") (pin "1") (pinfunction "DO_1") (pintype "output"))
      (node (ref "U49") (pin "3") (pinfunction "DI_3") (pintype "input"))
    )
    (net (code "16") (name "/DO15") (class "Default")
      (node (ref "U52") (pin "1") (pinfunction "DO_1") (pintype "output"))
      (node (ref "U61") (pin "3") (pinfunction "DI_3") (pintype "input"))
    )
    (net (code "17") (name "/DOUT") (class "Default")
      (node (ref "U64") (pin "1") (pinfunction "DO_1") (pintype "output"))
    )
    (net (code "18") (name "GND") (class "Default")
      (node (ref "C1") (pin "1") (pinfunction "1_1") (pintype "passive"))
      (node (ref "C10") (pin "1") (pinfunction "1_1") (pintype "passive"))
      (node (ref "C11") (pin "1") (pinfunction "1_1") (pintype "passive"))
      (node (ref "C12") (pin "1") (pinfunction "1_1") (pintype "passive"))
      (node (ref "C13") (pin "1") (pinfunction "1_1") (pintype "passive"))
      (node (ref "C14") (pin "1") (pinfunction "1_1") (pintype "passive"))
      (node (ref "C15") (pin "1") (pinfunction "1_1") (pintype "passive"))
      (node (ref "C16") (pin "1") (pinfunction "1_1") (pintype "passive"))
      (node (ref "C17") (pin "1") (pinfunction "1_1") (pintype "passive"))
      (node (ref "C18") (pin "1") (pinfunction "1_1") (pintype "passive"))
      (node (ref "C19") (pin "1") (pinfunction "1_1") (pintype "passive"))
      (node (ref "C2") (pin "1") (pinfunction "1_1") (pintype "passive"))
      (node (ref "C20") (pin "1") (pinfunction "1_1") (pintype "passive"))
      (node (ref "C21") (pin "1") (pinfunction "1_1") (pintype "passive"))
      (node (ref "C22") (pin "1") (pinfunction "1_1") (pintype "passive"))
      (node (ref "C23") (pin "1") (pinfunction "1_1") (pintype "passive"))
      (node (ref "C24") (pin "1") (pinfunction "1_1") (pintype "passive"))
      (node (ref "C25") (pin "1") (pinfunction "1_1") (pintype "passive"))
      (node (ref "C26") (pin "1") (pinfunction "1_1") (pintype "passive"))
      (node (ref "C27") (pin "1") (pinfunction "1_1") (pintype "passive"))
      (node (ref "C28") (pin "1") (pinfunction "1_1") (pintype "passive"))
      (node (ref "C29") (pin "1") (pinfunction "1_1") (pintype "passive"))
      (node (ref "C3") (pin "1") (pinfunction "1_1") (pintype "passive"))
      (node (ref "C30") (pin "1") (pinfunction "1_1") (pintype "passive"))
      (node (ref "C31") (pin "1") (pinfunction "1_1") (pintype "passive"))
      (node (ref "C32") (pin "1") (pinfunction "1_1") (pintype "passive"))
      (node (ref "C33") (pin "1") (pinfunction "1_1") (pintype "passive"))
      (node (ref "C34") (pin "1") (pinfunction "1_1") (pintype "passive"))
      (node (ref "C35") (pin "1") (pinfunction "1_1") (pintype "passive"))
      (node (ref "C36") (pin "1") (pinfunction "1_1") (pintype "passive"))
      (node (ref "C37") (pin "1") (pinfunction "1_1") (pintype "passive"))
      (node (ref "C38") (pin "1") (pinfunction "1_1") (pintype "passive"))
      (node (ref "C39") (pin "1") (pinfunction "1_1") (pintype "passive"))
      (node (ref "C4") (pin "1") (pinfunction "1_1") (pintype "passive"))
      (node (ref "C40") (pin "1") (pinfunction "1_1") (pintype "passive"))
      (node (ref "C41") (pin "1") (pinfunction "1_1") (pintype "passive"))
      (node (ref "C42") (pin "1") (pinfunction "1_1") (pintype "passive"))
      (node (ref "C43") (pin "1") (pinfunction "1_1") (pintype "passive"))
      (node (ref "C44") (pin "1") (pinfunction "1_1") (pintype "passive"))
      (node (ref "C45") (pin "1") (pinfunction "1_1") (pintype "passive"))
      (node (ref "C46") (pin "1") (pinfunction "1_1") (pintype "passive"))
      (node (ref "C47") (pin "1") (pinfunction "1_1") (pintype "passive"))
      (node (ref "C48") (pin "1") (pinfunction "1_1") (pintype "passive"))
      (node (ref "C49") (pin "1") (pinfunction "1_1") (pintype "passive"))
      (node (ref "C5") (pin "1") (pinfunction "1_1") (pintype "passive"))
      (node (ref "C50") (pin "1") (pinfunction "1_1") (pintype "passive"))
      (node (ref "C51") (pin "1") (pinfunction "1_1") (pintype "passive"))
      (node (ref "C52") (pin "1") (pinfunction "1_1") (pintype "passive"))
      (node (ref "C53") (pin "1") (pinfunction "1_1") (pintype "passive"))
      (node (ref "C54") (pin "1") (pinfunction "1_1") (pintype "passive"))
      (node (ref "C55") (pin "1") (pinfunction "1_1") (pintype "passive"))
      (node (ref "C56") (pin "1") (pinfunction "1_1") (pintype "passive"))
      (node (ref "C57") (pin "1") (pinfunction "1_1") (pintype "passive"))
      (node (ref "C58") (pin "1") (pinfunction "1_1") (pintype "passive"))
      (node (ref "C59") (pin "1") (pinfunction "1_1") (pintype "passive"))
      (node (ref "C6") (pin "1") (pinfunction "1_1") (pintype "passive"))
      (node (ref "C60") (pin "1") (pinfunction "1_1") (pintype "passive"))
      (node (ref "C61") (pin "1") (pinfunction "1_1") (pintype "passive"))
      (node (ref "C62") (pin "1") (pinfunction "1_1") (pintype "passive"))
      (node (ref "C63") (pin "1") (pinfunction "1_1") (pintype "passive"))
      (node (ref "C64") (pin "1") (pinfunction "1_1") (pintype "passive"))
      (node (ref "C7") (pin "1") (pinfunction "1_1") (pintype "passive"))
      (node (ref "C8") (pin "1") (pinfunction "1_1") (pintype "passive"))
      (node (ref "C9") (pin "1") (pinfunction "1_1") (pintype "passive"))
      (node (ref "U1") (pin "2") (pinfunction "GND_2") (pintype "power_in"))
      (node (ref "U10") (pin "2") (pinfunction "GND_2") (pintype "power_in"))
      (node (ref "U11") (pin "2") (pinfunction "GND_2") (pintype "power_in"))
      (node (ref "U12") (pin "2") (pinfunction "GND_2") (pintype "power_in"))
      (node (ref "U13") (pin "2") (pinfunction "GND_2") (pintype "power_in"))
      (node (ref "U14") (pin "2") (pinfunction "GND_2") (pintype "power_in"))
      (node (ref "U15") (pin "2") (pinfunction "GND_2") (pintype "power_in"))
      (node (ref "U16") (pin "2") (pinfunction "GND_2") (pintype "power_in"))
      (node (ref "U17") (pin "2") (pinfunction "GND_2") (pintype "power_in"))
      (node (ref "U18") (pin "2") (pinfunction "GND_2") (pintype "power_in"))
      (node (ref "U19") (pin "2") (pinfunction "GND_2") (pintype "power_in"))
      (node (ref "U2") (pin "2") (pinfunction "GND_2") (pintype "power_in"))
      (node (ref "U20") (pin "2") (pinfunction "GND_2") (pintype "power_in"))
      (node (ref "U21") (pin "2") (pinfunction "GND_2") (pintype "power_in"))
      (node (ref "U22") (pin "2") (pinfunction "GND_2") (pintype "power_in"))
      (node (ref "U23") (pin "2") (pinfunction "GND_2") (pintype "power_in"))
      (node (ref "U24") (pin "2") (pinfunction "GND_2") (pintype "power_in"))
      (node (ref "U25") (pin "2") (pinfunction "GND_2") (pintype "power_in"))
      (node (ref "U26") (pin "2") (pinfunction "GND_2") (pintype "power_in"))
      (node (ref "U27") (pin "2") (pinfunction "GND_2") (pintype "power_in"))
      (node (ref "U28") (pin "2") (pinfunction "GND_2") (pintype "power_in"))
      (node (ref "U29") (pin "2") (pinfunction "GND_2") (pintype "power_in"))
      (node (ref "U3") (pin "2") (pinfunction "GND_2") (pintype "power_in"))
      (node (ref "U30") (pin "2") (pinfunction "GND_2") (pintype "power_in"))
      (node (ref "U31") (pin "2") (pinfunction "GND_2") (pintype "power_in"))
      (node (ref "U32") (pin "2") (pinfunction "GND_2") (pintype "power_in"))
      (node (ref "U33") (pin "2") (pinfunction "GND_2") (pintype "power_in"))
      (node (ref "U34") (pin "2") (pinfunction "GND_2") (pintype "power_in"))
      (node (ref "U35") (pin "2") (pinfunction "GND_2") (pintype "power_in"))
      (node (ref "U36") (pin "2") (pinfunction "GND_2") (pintype "power_in"))
      (node (ref "U37") (pin "2") (pinfunction "GND_2") (pintype "power_in"))
      (node (ref "U38") (pin "2") (pinfunction "GND_2") (pintype "power_in"))
      (node (ref "U39") (pin "2") (pinfunction "GND_2") (pintype "power_in"))
      (node (ref "U4") (pin "2") (pinfunction "GND_2") (pintype "power_in"))
      (node (ref "U40") (pin "2") (pinfunction "GND_2") (pintype "power_in"))
      (node (ref "U41") (pin "2") (pinfunction "GND_2") (pintype "power_in"))
      (node (ref "U42") (pin "2") (pinfunction "GND_2") (pintype "power_in"))
      (node (ref "U43") (pin "2") (pinfunction "GND_2") (pintype "power_in"))
      (node (ref "U44") (pin "2") (pinfunction "GND_2") (pintype "power_in"))
      (node (ref "U45") (pin "2") (pinfunction "GND_2") (pintype "power_in"))
      (node (ref "U46") (pin "2") (pinfunction "GND_2") (pintype "power_in"))
      (node (ref "U47") (pin "2") (pinfunction "GND_2") (pintype "power_in"))
      (node (ref "U48") (pin "2") (pinfunction "GND_2") (pintype "power_in"))
      (node (ref "U49") (pin "2") (pinfunction "GND_2") (pintype "power_in"))
      (node (ref "U5") (pin "2") (pinfunction "GND_2") (pintype "power_in"))
      (node (ref "U50") (pin "2") (pinfunction "GND_2") (pintype "power_in"))
      (node (ref "U51") (pin "2") (pinfunction "GND_2") (pintype "power_in"))
      (node (ref "U52") (pin "2") (pinfunction "GND_2") (pintype "power_in"))
      (node (ref "U53") (pin "2") (pinfunction "GND_2") (pintype "power_in"))
      (node (ref "U54") (pin "2") (pinfunction "GND_2") (pintype "power_in"))
      (node (ref "U55") (pin "2") (pinfunction "GND_2") (pintype "power_in"))
      (node (ref "U56") (pin "2") (pinfunction "GND_2") (pintype "power_in"))
      (node (ref "U57") (pin "2") (pinfunction "GND_2") (pintype "power_in"))
      (node (ref "U58") (pin "2") (pinfunction "GND_2") (pintype "power_in"))
      (node (ref "U59") (pin "2") (pinfunction "GND_2") (pintype "power_in"))
      (node (ref "U6") (pin "2") (pinfunction "GND_2") (pintype "power_in"))
      (node (ref "U60") (pin "2") (pinfunction "GND_2") (pintype "power_in"))
      (node (ref "U61") (pin "2") (pinfunction "GND_2") (pintype "power_in"))
      (node (ref "U62") (pin "2") (pinfunction "GND_2") (pintype "power_in"))
      (node (ref "U63") (pin "2") (pinfunction "GND_2") (pintype "power_in"))
      (node (ref "U64") (pin "2") (pinfunction "GND_2") (pintype "power_in"))
      (node (ref "U7") (pin "2") (pinfunction "GND_2") (pintype "power_in"))
      (node (ref "U8") (pin "2") (pinfunction "GND_2") (pintype "power_in"))
      (node (ref "U9") (pin "2") (pinfunction "GND_2") (pintype "power_in"))
    )
    (net (code "19") (name "Net-(U1-DO)") (class "Default")
      (node (ref "U1") (pin "1") (pinfunction "DO_1") (pintype "output"))
      (node (ref "U2") (pin "3") (pinfunction "DI_3") (pintype "input"))
    )
    (net (code "20") (name "Net-(U2-DO)") (class "Default")
      (node (ref "U2") (pin "1") (pinfunction "DO_1") (pintype "output"))
      (node (ref "U3") (pin "3") (pinfunction "DI_3") (pintype "input"))
    )
    (net (code "21") (name "Net-(U3-DO)") (class "Default")
      (node (ref "U3") (pin "1") (pinfunction "DO_1") (pintype "output"))
      (node (ref "U4") (pin "3") (pinfunction "DI_3") (pintype "input"))
    )
    (net (code "22") (name "Net-(U5-DO)") (class "Default")
      (node (ref "U5") (pin "1") (pinfunction "DO_1") (pintype "output"))
      (node (ref "U6") (pin "3") (pinfunction "DI_3") (pintype "input"))
    )
    (net (code "23") (name "Net-(U6-DO)") (class "Default")
      (node (ref "U6") (pin "1") (pinfunction "DO_1") (pintype "output"))
      (node (ref "U7") (pin "3") (pinfunction "DI_3") (pintype "input"))
    )
    (net (code "24") (name "Net-(U7-DO)") (class "Default")
      (node (ref "U7") (pin "1") (pinfunction "DO_1") (pintype "output"))
      (node (ref "U8") (pin "3") (pinfunction "DI_3") (pintype "input"))
    )
    (net (code "25") (name "Net-(U10-DI)") (class "Default")
      (node (ref "U10") (pin "3") (pinfunction "DI_3") (pintype "input"))
      (node (ref "U9") (pin "1") (pinfunction "DO_1") (pintype "output"))
    )
    (net (code "26") (name "Net-(U10-DO)") (class "Default")
      (node (ref "U10") (pin "1") (pinfunction "DO_1") (pintype "output"))
      (node (ref "U11") (pin "3") (pinfunction "DI_3") (pintype "input"))
    )
    (net (code "27") (name "Net-(U11-DO)") (class "Default")
      (node (ref "U11") (pin "1") (pinfunction "DO_1") (pintype "output"))
      (node (ref "U12") (pin "3") (pinfunction "DI_3") (pintype "input"))
    )
    (net (code "28") (name "Net-(U13-DO)") (class "Default")
      (node (ref "U13") (pin "1") (pinfunction "DO_1") (pintype "output"))
      (node (ref "U14") (pin "3") (pinfunction "DI_3") (pintype "input"))
    )
    (net (code "29") (name "Net-(U14-DO)") (class "Default")
      (node (ref "U14") (pin "1") (pinfunction "DO_1") (pintype "output"))
      (node (ref "U15") (pin "3") (pinfunction "DI_3") (pintype "input"))
    )
    (net (code "30") (name "Net-(U15-DO)") (class "Default")
      (node (ref "U15") (pin "1") (pinfunction "DO_1") (pintype "output"))
      (node (ref "U16") (pin "3") (pinfunction "DI_3") (pintype "input"))
    )
    (net (code "31") (name "Net-(U17-DO)") (class "Default")
      (node (ref "U17") (pin "1") (pinfunction "DO_1") (pintype "output"))
      (node (ref "U18") (pin "3") (pinfunction "DI_3") (pintype "input"))
    )
    (net (code "32") (name "Net-(U18-DO)") (class "Default")
      (node (ref "U18") (pin "1") (pinfunction "DO_1") (pintype "output"))
      (node (ref "U19") (pin "3") (pinfunction "DI_3") (pintype "input"))
    )
    (net (code "33") (name "Net-(U19-DO)") (class "Default")
      (node (ref "U19") (pin "1") (pinfunction "DO_1") (pintype "output"))
      (node (ref "U20") (pin "3") (pinfunction "DI_3") (pintype "input"))
    )
    (net (code "34") (name "Net-(U21-DO)") (class "Default")
      (node (ref "U21") (pin "1") (pinfunction "DO_1") (pintype "output"))
      (node (ref "U22") (pin "3") (pinfunction "DI_3") (pintype "input"))
    )
    (net (code "35") (name "Net-(U22-DO)") (class "Default")
      (node (ref "U22") (pin "1") (pinfunction "DO_1") (pintype "output"))
      (node (ref "U23") (pin "3") (pinfunction "DI_3") (pintype "input"))
    )
    (net (code "36") (name "Net-(U23-DO)") (class "Default")
      (node (ref "U23") (pin "1") (pinfunction "DO_1") (pintype "output"))
      (node (ref "U24") (pin "3") (pinfunction "DI_3") (pintype "input"))
    )
    (net (code "37") (name "Net-(U25-DO)") (class "Default")
      (node (ref "U25") (pin "1") (pinfunction "DO_1") (pintype "output"))
      (node (ref "U26") (pin "3") (pinfunction "DI_3") (pintype "input"))
    )
    (net (code "38") (name "Net-(U26-DO)") (class "Default")
      (node (ref "U26") (pin "1") (pinfunction "DO_1") (pintype "output"))
      (node (ref "U27") (pin "3") (pinfunction "DI_3") (pintype "input"))
    )
    (net (code "39") (name "Net-(U27-DO)") (class "Default")
      (node (ref "U27") (pin "1") (pinfunction "DO_1") (pintype "output"))
      (node (ref "U28") (pin "3") (pinfunction "DI_3") (pintype "input"))
    )
    (net (code "40") (name "Net-(U29-DO)") (class "Default")
      (node (ref "U29") (pin "1") (pinfunction "DO_1") (pintype "output"))
      (node (ref "U30") (pin "3") (pinfunction "DI_3") (pintype "input"))
    )
    (net (code "41") (name "Net-(U30-DO)") (class "Default")
      (node (ref "U30") (pin "1") (pinfunction "DO_1") (pintype "output"))
      (node (ref "U31") (pin "3") (pinfunction "DI_3") (pintype "input"))
    )
    (net (code "42") (name "Net-(U31-DO)") (class "Default")
      (node (ref "U31") (pin "1") (pinfunction "DO_1") (pintype "output"))
      (node (ref "U32") (pin "3") (pinfunction "DI_3") (pintype "input"))
    )
    (net (code "43") (name "Net-(U33-DO)") (class "Default")
      (node (ref "U33") (pin "1") (pinfunction "DO_1") (pintype "output"))
      (node (ref "U34") (pin "3") (pinfunction "DI_3") (pintype "input"))
    )
    (net (code "44") (name "Net-(U34-DO)") (class "Default")
      (node (ref "U34") (pin "1") (pinfunction "DO_1") (pintype "output"))
      (node (ref "U35") (pin "3") (pinfunction "DI_3") (pintype "input"))
    )
    (net (code "45") (name "Net-(U35-DO)") (class "Default")
      (node (ref "U35") (pin "1") (pinfunction "DO_1") (pintype "output"))
      (node (ref "U36") (pin "3") (pinfunction "DI_3") (pintype "input"))
    )
    (net (code "46") (name "Net-(U37-DO)") (class "Default")
      (node (ref "U37") (pin "1") (pinfunction "DO_1") (pintype "output"))
      (node (ref "U38") (pin "3") (pinfunction "DI_3") (pintype "input"))
    )
    (net (code "47") (name "Net-(U38-DO)") (class "Default")
      (node (ref "U38") (pin "1") (pinfunction "DO_1") (pintype "output"))
      (node (ref "U39") (pin "3") (pinfunction "DI_3") (pintype "input"))
    )
    (net (code "48") (name "Net-(U39-DO)") (class "Default")
      (node (ref "U39") (pin "1") (pinfunction "DO_1") (pintype "output"))
      (node (ref "U40") (pin "3") (pinfunction "DI_3") (pintype "input"))
    )
    (net (code "49") (name "Net-(U41-DO)") (class "Default")
      (node (ref "U41") (pin "1") (pinfunction "DO_1") (pintype "output"))
      (node (ref "U42") (pin "3") (pinfunction "DI_3") (pintype "input"))
    )
    (net (code "50") (name "Net-(U42-DO)") (class "Default")
      (node (ref "U42") (pin "1") (pinfunction "DO_1") (pintype "output"))
      (node (ref "U43") (pin "3") (pinfunction "DI_3") (pintype "input"))
    )
    (net (code "51") (name "Net-(U43-DO)") (class "Default")
      (node (ref "U43") (pin "1") (pinfunction "DO_1") (pintype "output"))
      (node (ref "U44") (pin "3") (pinfunction "DI_3") (pintype "input"))
    )
    (net (code "52") (name "Net-(U45-DO)") (class "Default")
      (node (ref "U45") (pin "1") (pinfunction "DO_1") (pintype "output"))
      (node (ref "U46") (pin "3") (pinfunction "DI_3") (pintype "input"))
    )
    (net (code "53") (name "Net-(U46-DO)") (class "Default")
      (node (ref "U46") (pin "1") (pinfunction "DO_1") (pintype "output"))
      (node (ref "U47") (pin "3") (pinfunction "DI_3") (pintype "input"))
    )
    (net (code "54") (name "Net-(U47-DO)") (class "Default")
      (node (ref "U47") (pin "1") (pinfunction "DO_1") (pintype "output"))
      (node (ref "U48") (pin "3") (pinfunction "DI_3") (pintype "input"))
    )
    (net (code "55") (name "Net-(U49-DO)") (class "Default")
      (node (ref "U49") (pin "1") (pinfunction "DO_1") (pintype "output"))
      (node (ref "U50") (pin "3") (pinfunction "DI_3") (pintype "input"))
    )
    (net (code "56") (name "Net-(U50-DO)") (class "Default")
      (node (ref "U50") (pin "1") (pinfunction "DO_1") (pintype "output"))
      (node (ref "U51") (pin "3") (pinfunction "DI_3") (pintype "input"))
    )
    (net (code "57") (name "Net-(U51-DO)") (class "Default")
      (node (ref "U51") (pin "1") (pinfunction "DO_1") (pintype "output"))
      (node (ref "U52") (pin "3") (pinfunction "DI_3") (pintype "input"))
    )
    (net (code "58") (name "Net-(U53-DO)") (class "Default")
      (node (ref "U53") (pin "1") (pinfunction "DO_1") (pintype "output"))
      (node (ref "U54") (pin "3") (pinfunction "DI_3") (pintype "input"))
    )
    (net (code "59") (name "Net-(U54-DO)") (class "Default")
      (node (ref "U54") (pin "1") (pinfunction "DO_1") (pintype "output"))
      (node (ref "U55") (pin "3") (pinfunction "DI_3") (pintype "input"))
    )
    (net (code "60") (name "Net-(U55-DO)") (class "Default")
      (node (ref "U55") (pin "1") (pinfunction "DO_1") (pintype "output"))
      (node (ref "U56") (pin "3") (pinfunction "DI_3") (pintype "input"))
    )
    (net (code "61") (name "Net-(U57-DO)") (class "Default")
      (node (ref "U57") (pin "1") (pinfunction "DO_1") (pintype "output"))
      (node (ref "U58") (pin "3") (pinfunction "DI_3") (pintype "input"))
    )
    (net (code "62") (name "Net-(U58-DO)") (class "Default")
      (node (ref "U58") (pin "1") (pinfunction "DO_1") (pintype "output"))
      (node (ref "U59") (pin "3") (pinfunction "DI_3") (pintype "input"))
    )
    (net (code "63") (name "Net-(U59-DO)") (class "Default")
      (node (ref "U59") (pin "1") (pinfunction "DO_1") (pintype "output"))
      (node (ref "U60") (pin "3") (pinfunction "DI_3") (pintype "input"))
    )
    (net (code "64") (name "Net-(U61-DO)") (class "Default")
      (node (ref "U61") (pin "1") (pinfunction "DO_1") (pintype "output"))
      (node (ref "U62") (pin "3") (pinfunction "DI_3") (pintype "input"))
    )
    (net (code "65") (name "Net-(U62-DO)") (class "Default")
      (node (ref "U62") (pin "1") (pinfunction "DO_1") (pintype "output"))
      (node (ref "U63") (pin "3") (pinfunction "DI_3") (pintype "input"))
    )
    (net (code "66") (name "Net-(U63-DO)") (class "Default")
      (node (ref "U63") (pin "1") (pinfunction "DO_1") (pintype "output"))
      (node (ref "U64") (pin "3") (pinfunction "DI_3") (pintype "input"))
    )
    (net (code "67") (name "VCC5V") (class "Default")
      (node (ref "C1") (pin "2") (pinfunction "2_2") (pintype "passive"))
      (node (ref "C10") (pin "2") (pinfunction "2_2") (pintype "passive"))
      (node (ref "C11") (pin "2") (pinfunction "2_2") (pintype "passive"))
      (node (ref "C12") (pin "2") (pinfunction "2_2") (pintype "passive"))
      (node (ref "C13") (pin "2") (pinfunction "2_2") (pintype "passive"))
      (node (ref "C14") (pin "2") (pinfunction "2_2") (pintype "passive"))
      (node (ref "C15") (pin "2") (pinfunction "2_2") (pintype "passive"))
      (node (ref "C16") (pin "2") (pinfunction "2_2") (pintype "passive"))
      (node (ref "C17") (pin "2") (pinfunction "2_2") (pintype "passive"))
      (node (ref "C18") (pin "2") (pinfunction "2_2") (pintype "passive"))
      (node (ref "C19") (pin "2") (pinfunction "2_2") (pintype "passive"))
      (node (ref "C2") (pin "2") (pinfunction "2_2") (pintype "passive"))
      (node (ref "C20") (pin "2") (pinfunction "2_2") (pintype "passive"))
      (node (ref "C21") (pin "2") (pinfunction "2_2") (pintype "passive"))
      (node (ref "C22") (pin "2") (pinfunction "2_2") (pintype "passive"))
      (node (ref "C23") (pin "2") (pinfunction "2_2") (pintype "passive"))
      (node (ref "C24") (pin "2") (pinfunction "2_2") (pintype "passive"))
      (node (ref "C25") (pin "2") (pinfunction "2_2") (pintype "passive"))
      (node (ref "C26") (pin "2") (pinfunction "2_2") (pintype "passive"))
      (node (ref "C27") (pin "2") (pinfunction "2_2") (pintype "passive"))
      (node (ref "C28") (pin "2") (pinfunction "2_2") (pintype "passive"))
      (node (ref "C29") (pin "2") (pinfunction "2_2") (pintype "passive"))
      (node (ref "C3") (pin "2") (pinfunction "2_2") (pintype "passive"))
      (node (ref "C30") (pin "2") (pinfunction "2_2") (pintype "passive"))
      (node (ref "C31") (pin "2") (pinfunction "2_2") (pintype "passive"))
      (node (ref "C32") (pin "2") (pinfunction "2_2") (pintype "passive"))
      (node (ref "C33") (pin "2") (pinfunction "2_2") (pintype "passive"))
      (node (ref "C34") (pin "2") (pinfunction "2_2") (pintype "passive"))
      (node (ref "C35") (pin "2") (pinfunction "2_2") (pintype "passive"))
      (node (ref "C36") (pin "2") (pinfunction "2_2") (pintype "passive"))
      (node (ref "C37") (pin "2") (pinfunction "2_2") (pintype "passive"))
      (node (ref "C38") (pin "2") (pinfunction "2_2") (pintype "passive"))
      (node (ref "C39") (pin "2") (pinfunction "2_2") (pintype "passive"))
      (node (ref "C4") (pin "2") (pinfunction "2_2") (pintype "passive"))
      (node (ref "C40") (pin "2") (pinfunction "2_2") (pintype "passive"))
      (node (ref "C41") (pin "2") (pinfunction "2_2") (pintype "passive"))
      (node (ref "C42") (pin "2") (pinfunction "2_2") (pintype "passive"))
      (node (ref "C43") (pin "2") (pinfunction "2_2") (pintype "passive"))
      (node (ref "C44") (pin "2") (pinfunction "2_2") (pintype "passive"))
      (node (ref "C45") (pin "2") (pinfunction "2_2") (pintype "passive"))
      (node (ref "C46") (pin "2") (pinfunction "2_2") (pintype "passive"))
      (node (ref "C47") (pin "2") (pinfunction "2_2") (pintype "passive"))
      (node (ref "C48") (pin "2") (pinfunction "2_2") (pintype "passive"))
      (node (ref "C49") (pin "2") (pinfunction "2_2") (pintype "passive"))
      (node (ref "C5") (pin "2") (pinfunction "2_2") (pintype "passive"))
      (node (ref "C50") (pin "2") (pinfunction "2_2") (pintype "passive"))
      (node (ref "C51") (pin "2") (pinfunction "2_2") (pintype "passive"))
      (node (ref "C52") (pin "2") (pinfunction "2_2") (pintype "passive"))
      (node (ref "C53") (pin "2") (pinfunction "2_2") (pintype "passive"))
      (node (ref "C54") (pin "2") (pinfunction "2_2") (pintype "passive"))
      (node (ref "C55") (pin "2") (pinfunction "2_2") (pintype "passive"))
      (node (ref "C56") (pin "2") (pinfunction "2_2") (pintype "passive"))
      (node (ref "C57") (pin "2") (pinfunction "2_2") (pintype "passive"))
      (node (ref "C58") (pin "2") (pinfunction "2_2") (pintype "passive"))
      (node (ref "C59") (pin "2") (pinfunction "2_2") (pintype "passive"))
      (node (ref "C6") (pin "2") (pinfunction "2_2") (pintype "passive"))
      (node (ref "C60") (pin "2") (pinfunction "2_2") (pintype "passive"))
      (node (ref "C61") (pin "2") (pinfunction "2_2") (pintype "passive"))
      (node (ref "C62") (pin "2") (pinfunction "2_2") (pintype "passive"))
      (node (ref "C63") (pin "2") (pinfunction "2_2") (pintype "passive"))
      (node (ref "C64") (pin "2") (pinfunction "2_2") (pintype "passive"))
      (node (ref "C7") (pin "2") (pinfunction "2_2") (pintype "passive"))
      (node (ref "C8") (pin "2") (pinfunction "2_2") (pintype "passive"))
      (node (ref "C9") (pin "2") (pinfunction "2_2") (pintype "passive"))
      (node (ref "U1") (pin "4") (pinfunction "VDD_4") (pintype "power_in"))
      (node (ref "U10") (pin "4") (pinfunction "VDD_4") (pintype "power_in"))
      (node (ref "U11") (pin "4") (pinfunction "VDD_4") (pintype "power_in"))
      (node (ref "U12") (pin "4") (pinfunction "VDD_4") (pintype "power_in"))
      (node (ref "U13") (pin "4") (pinfunction "VDD_4") (pintype "power_in"))
      (node (ref "U14") (pin "4") (pinfunction "VDD_4") (pintype "power_in"))
      (node (ref "U15") (pin "4") (pinfunction "VDD_4") (pintype "power_in"))
      (node (ref "U16") (pin "4") (pinfunction "VDD_4") (pintype "power_in"))
      (node (ref "U17") (pin "4") (pinfunction "VDD_4") (pintype "power_in"))
      (node (ref "U18") (pin "4") (pinfunction "VDD_4") (pintype "power_in"))
      (node (ref "U19") (pin "4") (pinfunction "VDD_4") (pintype "power_in"))
      (node (ref "U2") (pin "4") (pinfunction "VDD_4") (pintype "power_in"))
      (node (ref "U20") (pin "4") (pinfunction "VDD_4") (pintype "power_in"))
      (node (ref "U21") (pin "4") (pinfunction "VDD_4") (pintype "power_in"))
      (node (ref "U22") (pin "4") (pinfunction "VDD_4") (pintype "power_in"))
      (node (ref "U23") (pin "4") (pinfunction "VDD_4") (pintype "power_in"))
      (node (ref "U24") (pin "4") (pinfunction "VDD_4") (pintype "power_in"))
      (node (ref "U25") (pin "4") (pinfunction "VDD_4") (pintype "power_in"))
      (node (ref "U26") (pin "4") (pinfunction "VDD_4") (pintype "power_in"))
      (node (ref "U27") (pin "4") (pinfunction "VDD_4") (pintype "power_in"))
      (node (ref "U28") (pin "4") (pinfunction "VDD_4") (pintype "power_in"))
      (node (ref "U29") (pin "4") (pinfunction "VDD_4") (pintype "power_in"))
      (node (ref "U3") (pin "4") (pinfunction "VDD_4") (pintype "power_in"))
      (node (ref "U30") (pin "4") (pinfunction "VDD_4") (pintype "power_in"))
      (node (ref "U31") (pin "4") (pinfunction "VDD_4") (pintype "power_in"))
      (node (ref "U32") (pin "4") (pinfunction "VDD_4") (pintype "power_in"))
      (node (ref "U33") (pin "4") (pinfunction "VDD_4") (pintype "power_in"))
      (node (ref "U34") (pin "4") (pinfunction "VDD_4") (pintype "power_in"))
      (node (ref "U35") (pin "4") (pinfunction "VDD_4") (pintype "power_in"))
      (node (ref "U36") (pin "4") (pinfunction "VDD_4") (pintype "power_in"))
      (node (ref "U37") (pin "4") (pinfunction "VDD_4") (pintype "power_in"))
      (node (ref "U38") (pin "4") (pinfunction "VDD_4") (pintype "power_in"))
      (node (ref "U39") (pin "4") (pinfunction "VDD_4") (pintype "power_in"))
      (node (ref "U4") (pin "4") (pinfunction "VDD_4") (pintype "power_in"))
      (node (ref "U40") (pin "4") (pinfunction "VDD_4") (pintype "power_in"))
      (node (ref "U41") (pin "4") (pinfunction "VDD_4") (pintype "power_in"))
      (node (ref "U42") (pin "4") (pinfunction "VDD_4") (pintype "power_in"))
      (node (ref "U43") (pin "4") (pinfunction "VDD_4") (pintype "power_in"))
      (node (ref "U44") (pin "4") (pinfunction "VDD_4") (pintype "power_in"))
      (node (ref "U45") (pin "4") (pinfunction "VDD_4") (pintype "power_in"))
      (node (ref "U46") (pin "4") (pinfunction "VDD_4") (pintype "power_in"))
      (node (ref "U47") (pin "4") (pinfunction "VDD_4") (pintype "power_in"))
      (node (ref "U48") (pin "4") (pinfunction "VDD_4") (pintype "power_in"))
      (node (ref "U49") (pin "4") (pinfunction "VDD_4") (pintype "power_in"))
      (node (ref "U5") (pin "4") (pinfunction "VDD_4") (pintype "power_in"))
      (node (ref "U50") (pin "4") (pinfunction "VDD_4") (pintype "power_in"))
      (node (ref "U51") (pin "4") (pinfunction "VDD_4") (pintype "power_in"))
      (node (ref "U52") (pin "4") (pinfunction "VDD_4") (pintype "power_in"))
      (node (ref "U53") (pin "4") (pinfunction "VDD_4") (pintype "power_in"))
      (node (ref "U54") (pin "4") (pinfunction "VDD_4") (pintype "power_in"))
      (node (ref "U55") (pin "4") (pinfunction "VDD_4") (pintype "power_in"))
      (node (ref "U56") (pin "4") (pinfunction "VDD_4") (pintype "power_in"))
      (node (ref "U57") (pin "4") (pinfunction "VDD_4") (pintype "power_in"))
      (node (ref "U58") (pin "4") (pinfunction "VDD_4") (pintype "power_in"))
      (node (ref "U59") (pin "4") (pinfunction "VDD_4") (pintype "power_in"))
      (node (ref "U6") (pin "4") (pinfunction "VDD_4") (pintype "power_in"))
      (node (ref "U60") (pin "4") (pinfunction "VDD_4") (pintype "power_in"))
      (node (ref "U61") (pin "4") (pinfunction "VDD_4") (pintype "power_in"))
      (node (ref "U62") (pin "4") (pinfunction "VDD_4") (pintype "power_in"))
      (node (ref "U63") (pin "4") (pinfunction "VDD_4") (pintype "power_in"))
      (node (ref "U64") (pin "4") (pinfunction "VDD_4") (pintype "power_in"))
      (node (ref "U7") (pin "4") (pinfunction "VDD_4") (pintype "power_in"))
      (node (ref "U8") (pin "4") (pinfunction "VDD_4") (pintype "power_in"))
      (node (ref "U9") (pin "4") (pinfunction "VDD_4") (pintype "power_in"))
    )
  )
)
